# Sender.net
KiCad netlist of a schematic drawn in EAGLE
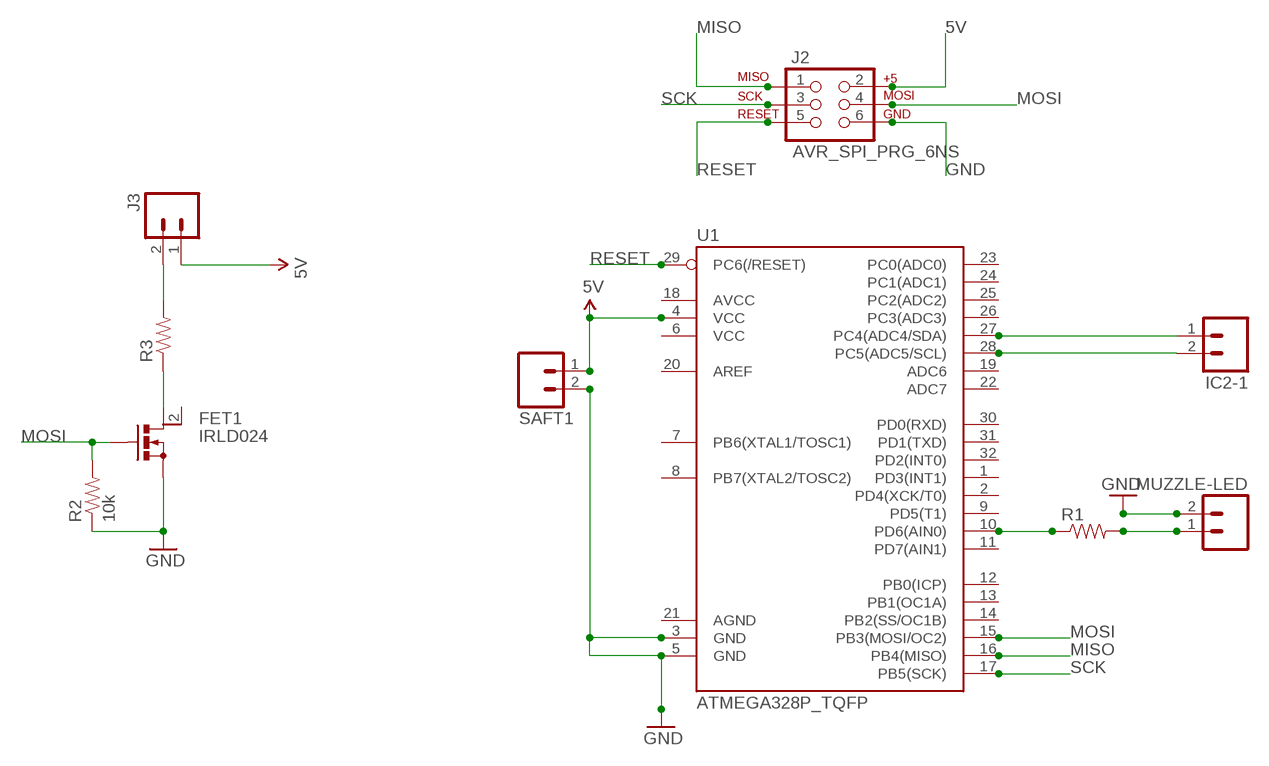
[diagram p0: schematic, sheet 1]

(export (version "E")
  (design (tool "Eeschema 10.0.6"))
  (components
    (comp (ref "FET1")
      (value "IRLD024")
      (footprint "eagle-import:DIL04")
      (libsource (lib "eagle-import") (part "IRLD024"))
    )
    (comp (ref "IC2-1")
      (value "M02-JST-2-PTH-NO_SILK")
      (footprint "eagle-import:JST-2-PTH-NS")
      (libsource (lib "eagle-import") (part "M02-JST-2-PTH-NO_SILK"))
    )
    (comp (ref "J2")
      (value "AVR_SPI_PRG_6NS")
      (footprint "eagle-import:2X3-NS")
      (libsource (lib "eagle-import") (part "AVR_SPI_PRG_6NS"))
    )
    (comp (ref "J3")
      (value "M02-JST-2-PTH-NO_SILK")
      (footprint "eagle-import:JST-2-PTH-NS")
      (libsource (lib "eagle-import") (part "M02-JST-2-PTH-NO_SILK"))
    )
    (comp (ref "MUZZLE-LED")
      (value "M02-JST-2-PTH-NO_SILK")
      (footprint "eagle-import:JST-2-PTH-NS")
      (libsource (lib "eagle-import") (part "M02-JST-2-PTH-NO_SILK"))
    )
    (comp (ref "R1")
      (value "RESISTOR0603-RES")
      (footprint "eagle-import:0603-RES")
      (libsource (lib "eagle-import") (part "RESISTOR0603-RES"))
    )
    (comp (ref "R2")
      (value "10k")
      (footprint "eagle-import:0603-RES")
      (libsource (lib "eagle-import") (part "RESISTOR0603-RES"))
    )
    (comp (ref "R3")
      (value "RESISTORPTH-2W")
      (footprint "eagle-import:AXIAL-0.8")
      (libsource (lib "eagle-import") (part "RESISTORPTH-2W"))
    )
    (comp (ref "SAFT1")
      (value "M02-JST-2-PTH-NO_SILK")
      (footprint "eagle-import:JST-2-PTH-NS")
      (libsource (lib "eagle-import") (part "M02-JST-2-PTH-NO_SILK"))
    )
    (comp (ref "U1")
      (value "ATMEGA328P_TQFP")
      (footprint "eagle-import:TQFP32-08")
      (libsource (lib "eagle-import") (part "ATMEGA328P_TQFP"))
    )
  )
  (nets
    (net (code "1") (name "/MISO") (class "Default")
      (node (ref "J2") (pin "1") (pinfunction "1_1") (pintype "passive"))
      (node (ref "U1") (pin "16") (pinfunction "PB4(MISO)_16") (pintype "bidirectional"))
    )
    (net (code "2") (name "/MOSI") (class "Default")
      (node (ref "FET1") (pin "3") (pinfunction "G_3") (pintype "passive"))
      (node (ref "J2") (pin "4") (pinfunction "4_4") (pintype "passive"))
      (node (ref "R2") (pin "2") (pinfunction "2_2") (pintype "passive"))
      (node (ref "U1") (pin "15") (pinfunction "PB3(MOSI/OC2)_15") (pintype "bidirectional"))
    )
    (net (code "3") (name "/RESET") (class "Default")
      (node (ref "J2") (pin "5") (pinfunction "5_5") (pintype "passive"))
      (node (ref "U1") (pin "29") (pinfunction "PC6(/RESET)_29") (pintype "bidirectional"))
    )
    (net (code "4") (name "/SCK") (class "Default")
      (node (ref "J2") (pin "3") (pinfunction "3_3") (pintype "passive"))
      (node (ref "U1") (pin "17") (pinfunction "PB5(SCK)_17") (pintype "bidirectional"))
    )
    (net (code "5") (name "5V") (class "Default")
      (node (ref "J2") (pin "2") (pinfunction "2_2") (pintype "passive"))
      (node (ref "J3") (pin "1") (pinfunction "1_1") (pintype "passive"))
      (node (ref "SAFT1") (pin "1") (pinfunction "1_1") (pintype "passive"))
      (node (ref "U1") (pin "4") (pinfunction "VCC_4") (pintype "bidirectional"))
    )
    (net (code "6") (name "GND") (class "Default")
      (node (ref "FET1") (pin "4") (pinfunction "S_4") (pintype "passive"))
      (node (ref "J2") (pin "6") (pinfunction "6_6") (pintype "passive"))
      (node (ref "MUZZLE-LED") (pin "2") (pinfunction "2_2") (pintype "passive"))
      (node (ref "R2") (pin "1") (pinfunction "1_1") (pintype "passive"))
      (node (ref "SAFT1") (pin "2") (pinfunction "2_2") (pintype "passive"))
      (node (ref "U1") (pin "3") (pinfunction "GND_3") (pintype "bidirectional"))
      (node (ref "U1") (pin "5") (pinfunction "GND_5") (pintype "bidirectional"))
    )
    (net (code "7") (name "Net-(FET1-D1)") (class "Default")
      (node (ref "FET1") (pin "1") (pinfunction "D1_1") (pintype "passive"))
      (node (ref "R3") (pin "P$1") (pinfunction "1_P$1") (pintype "passive"))
    )
    (net (code "8") (name "Net-(MUZZLE-LED-Pad1)") (class "Default")
      (node (ref "MUZZLE-LED") (pin "1") (pinfunction "1_1") (pintype "passive"))
      (node (ref "R1") (pin "2") (pinfunction "2_2") (pintype "passive"))
    )
    (net (code "9") (name "Net-(R3-2)") (class "Default")
      (node (ref "J3") (pin "2") (pinfunction "2_2") (pintype "passive"))
      (node (ref "R3") (pin "P$2") (pinfunction "2_P$2") (pintype "passive"))
    )
    (net (code "10") (name "Net-(U1-PC4(ADC4{slash}SDA))") (class "Default")
      (node (ref "IC2-1") (pin "1") (pinfunction "1_1") (pintype "passive"))
      (node (ref "U1") (pin "27") (pinfunction "PC4(ADC4/SDA)_27") (pintype "bidirectional"))
    )
    (net (code "11") (name "Net-(U1-PC5(ADC5{slash}SCL))") (class "Default")
      (node (ref "IC2-1") (pin "2") (pinfunction "2_2") (pintype "passive"))
      (node (ref "U1") (pin "28") (pinfunction "PC5(ADC5/SCL)_28") (pintype "bidirectional"))
    )
    (net (code "12") (name "Net-(U1-PD6(AIN0))") (class "Default")
      (node (ref "R1") (pin "1") (pinfunction "1_1") (pintype "passive"))
      (node (ref "U1") (pin "10") (pinfunction "PD6(AIN0)_10") (pintype "bidirectional"))
    )
    (net (code "13") (name "unconnected-(FET1-D2-Pad2)") (class "Default")
      (node (ref "FET1") (pin "2") (pinfunction "D2_2") (pintype "passive"))
    )
    (net (code "14") (name "unconnected-(U1-ADC6-Pad19)") (class "Default")
      (node (ref "U1") (pin "19") (pinfunction "ADC6_19") (pintype "bidirectional"))
    )
    (net (code "15") (name "unconnected-(U1-ADC7-Pad22)") (class "Default")
      (node (ref "U1") (pin "22") (pinfunction "ADC7_22") (pintype "bidirectional"))
    )
    (net (code "16") (name "unconnected-(U1-AGND-Pad21)") (class "Default")
      (node (ref "U1") (pin "21") (pinfunction "AGND_21") (pintype "bidirectional"))
    )
    (net (code "17") (name "unconnected-(U1-AREF-Pad20)") (class "Default")
      (node (ref "U1") (pin "20") (pinfunction "AREF_20") (pintype "bidirectional"))
    )
    (net (code "18") (name "unconnected-(U1-AVCC-Pad18)") (class "Default")
      (node (ref "U1") (pin "18") (pinfunction "AVCC_18") (pintype "bidirectional"))
    )
    (net (code "19") (name "unconnected-(U1-PB0(ICP)-Pad12)") (class "Default")
      (node (ref "U1") (pin "12") (pinfunction "PB0(ICP)_12") (pintype "bidirectional"))
    )
    (net (code "20") (name "unconnected-(U1-PB1(OC1A)-Pad13)") (class "Default")
      (node (ref "U1") (pin "13") (pinfunction "PB1(OC1A)_13") (pintype "bidirectional"))
    )
    (net (code "21") (name "unconnected-(U1-PB2(SS{slash}OC1B)-Pad14)") (class "Default")
      (node (ref "U1") (pin "14") (pinfunction "PB2(SS/OC1B)_14") (pintype "bidirectional"))
    )
    (net (code "22") (name "unconnected-(U1-PB6(XTAL1{slash}TOSC1)-Pad7)") (class "Default")
      (node (ref "U1") (pin "7") (pinfunction "PB6(XTAL1/TOSC1)_7") (pintype "bidirectional"))
    )
    (net (code "23") (name "unconnected-(U1-PB7(XTAL2{slash}TOSC2)-Pad8)") (class "Default")
      (node (ref "U1") (pin "8") (pinfunction "PB7(XTAL2/TOSC2)_8") (pintype "bidirectional"))
    )
    (net (code "24") (name "unconnected-(U1-PC0(ADC0)-Pad23)") (class "Default")
      (node (ref "U1") (pin "23") (pinfunction "PC0(ADC0)_23") (pintype "bidirectional"))
    )
    (net (code "25") (name "unconnected-(U1-PC1(ADC1)-Pad24)") (class "Default")
      (node (ref "U1") (pin "24") (pinfunction "PC1(ADC1)_24") (pintype "bidirectional"))
    )
    (net (code "26") (name "unconnected-(U1-PC2(ADC2)-Pad25)") (class "Default")
      (node (ref "U1") (pin "25") (pinfunction "PC2(ADC2)_25") (pintype "bidirectional"))
    )
    (net (code "27") (name "unconnected-(U1-PC3(ADC3)-Pad26)") (class "Default")
      (node (ref "U1") (pin "26") (pinfunction "PC3(ADC3)_26") (pintype "bidirectional"))
    )
    (net (code "28") (name "unconnected-(U1-PD0(RXD)-Pad30)") (class "Default")
      (node (ref "U1") (pin "30") (pinfunction "PD0(RXD)_30") (pintype "bidirectional"))
    )
    (net (code "29") (name "unconnected-(U1-PD1(TXD)-Pad31)") (class "Default")
      (node (ref "U1") (pin "31") (pinfunction "PD1(TXD)_31") (pintype "bidirectional"))
    )
    (net (code "30") (name "unconnected-(U1-PD2(INT0)-Pad32)") (class "Default")
      (node (ref "U1") (pin "32") (pinfunction "PD2(INT0)_32") (pintype "bidirectional"))
    )
    (net (code "31") (name "unconnected-(U1-PD3(INT1)-Pad1)") (class "Default")
      (node (ref "U1") (pin "1") (pinfunction "PD3(INT1)_1") (pintype "bidirectional"))
    )
    (net (code "32") (name "unconnected-(U1-PD4(XCK{slash}T0)-Pad2)") (class "Default")
      (node (ref "U1") (pin "2") (pinfunction "PD4(XCK/T0)_2") (pintype "bidirectional"))
    )
    (net (code "33") (name "unconnected-(U1-PD5(T1)-Pad9)") (class "Default")
      (node (ref "U1") (pin "9") (pinfunction "PD5(T1)_9") (pintype "bidirectional"))
    )
    (net (code "34") (name "unconnected-(U1-PD7(AIN1)-Pad11)") (class "Default")
      (node (ref "U1") (pin "11") (pinfunction "PD7(AIN1)_11") (pintype "bidirectional"))
    )
    (net (code "35") (name "unconnected-(U1-VCC-Pad6)") (class "Default")
      (node (ref "U1") (pin "6") (pinfunction "VCC_6") (pintype "bidirectional"))
    )
  )
)
